# power_supply.net
KiCad netlist of a schematic drawn in Altium Designer
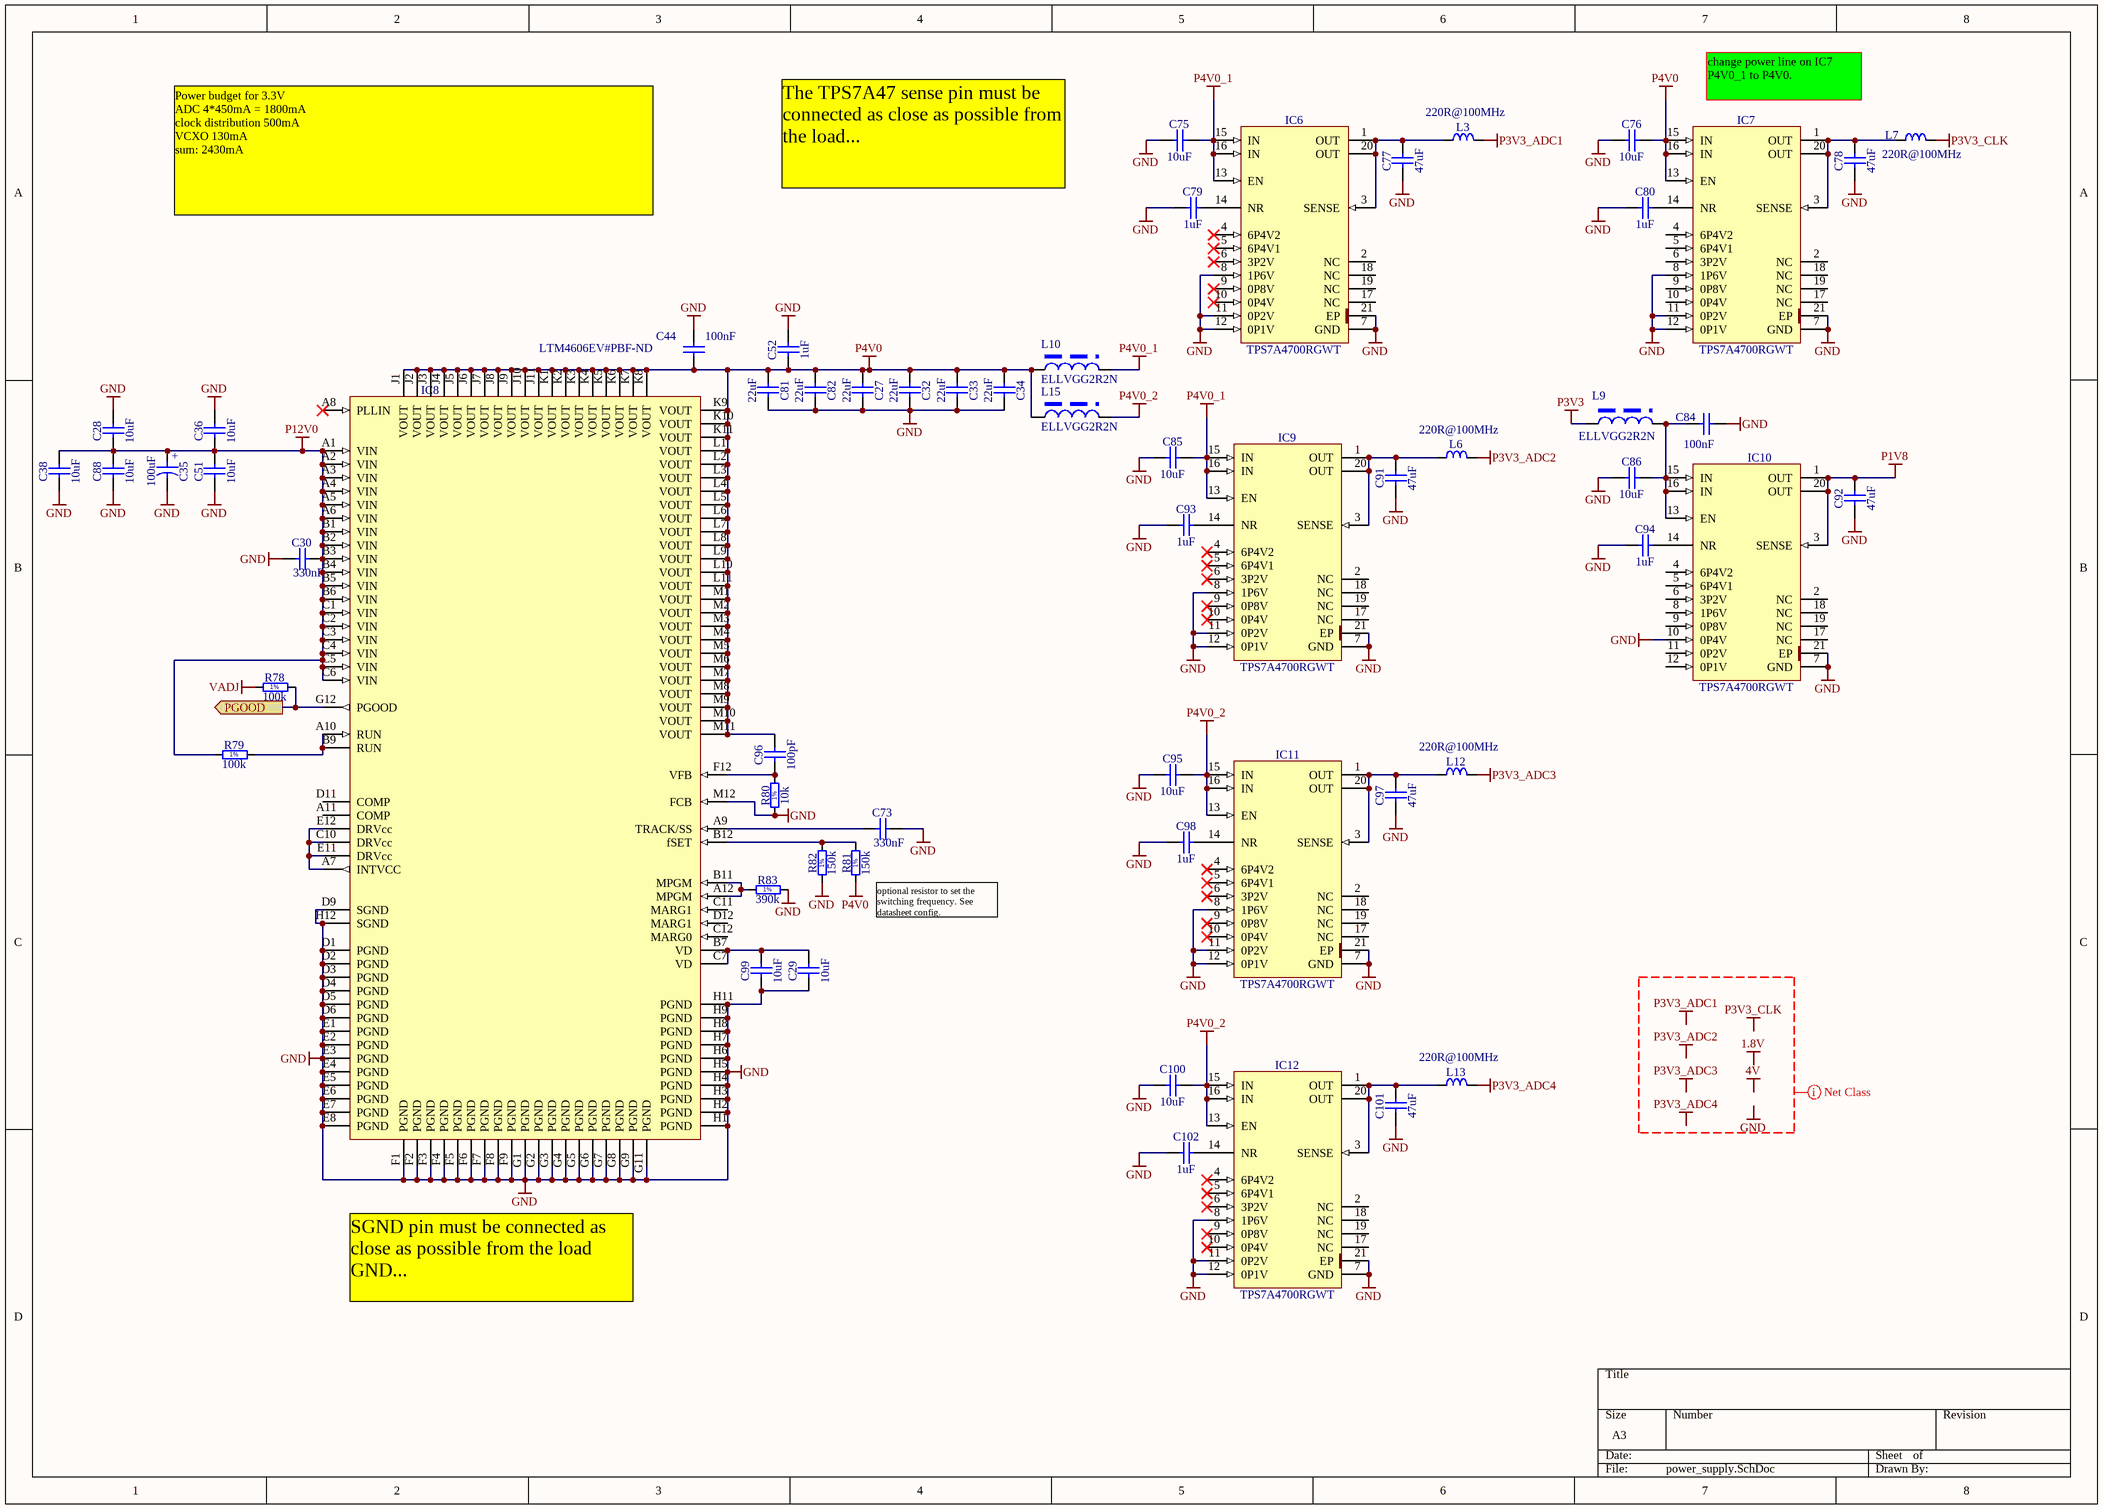
[diagram p0: power_supply.SchDoc]

(export (version "E")
  (design (tool "Eeschema 10.0.6"))
  (components
    (comp (ref "C27")
      (value "22uF")
      (footprint "CAPC3216X140N")
      (description "Non-polarised capacitor")
      (fields
        (field (name "PART NUMBER") "CC1206_22UF_6.3V_20%_X5R")
        (field (name "VOLTAGE") "6.3V")
        (field (name "AUTHOR") "CERN DEM JLC")
      )
      (libsource (lib "Capacitors") (part "Capacitor - non polarized"))
    )
    (comp (ref "C28")
      (value "10uF")
      (footprint "CAPC2012X135N")
      (description "Non-polarised capacitor")
      (fields
        (field (name "PART NUMBER") "CC0805_10UF_16V_10%_X5R")
        (field (name "VOLTAGE") "16V")
        (field (name "AUTHOR") "CERN DEM JLC")
      )
      (libsource (lib "Capacitors") (part "Capacitor - non polarized"))
    )
    (comp (ref "C29")
      (value "10uF")
      (footprint "CAPC2012X135N")
      (description "Non-polarised capacitor")
      (fields
        (field (name "PART NUMBER") "CC0805_10UF_16V_10%_X5R")
        (field (name "VOLTAGE") "16V")
        (field (name "AUTHOR") "CERN DEM JLC")
      )
      (libsource (lib "Capacitors") (part "Capacitor - non polarized"))
    )
    (comp (ref "C30")
      (value "330nF")
      (footprint "CAPC1608X87N")
      (description "Non-polarised capacitor")
      (fields
        (field (name "PART NUMBER") "CC0603_330NF_16V_10%_X5R")
        (field (name "VOLTAGE") "16V")
        (field (name "AUTHOR") "CERN DEM JLC")
      )
      (libsource (lib "Capacitors") (part "Capacitor - non polarized"))
    )
    (comp (ref "C32")
      (value "22uF")
      (footprint "CAPC3216X140N")
      (description "Non-polarised capacitor")
      (fields
        (field (name "PART NUMBER") "CC1206_22UF_6.3V_20%_X5R")
        (field (name "VOLTAGE") "6.3V")
        (field (name "AUTHOR") "CERN DEM JLC")
      )
      (libsource (lib "Capacitors") (part "Capacitor - non polarized"))
    )
    (comp (ref "C33")
      (value "22uF")
      (footprint "CAPC3216X140N")
      (description "Non-polarised capacitor")
      (fields
        (field (name "PART NUMBER") "CC1206_22UF_6.3V_20%_X5R")
        (field (name "VOLTAGE") "6.3V")
        (field (name "AUTHOR") "CERN DEM JLC")
      )
      (libsource (lib "Capacitors") (part "Capacitor - non polarized"))
    )
    (comp (ref "C34")
      (value "22uF")
      (footprint "CAPC3216X140N")
      (description "Non-polarised capacitor")
      (fields
        (field (name "PART NUMBER") "CC1206_22UF_6.3V_20%_X5R")
        (field (name "VOLTAGE") "6.3V")
        (field (name "AUTHOR") "CERN DEM JLC")
      )
      (libsource (lib "Capacitors") (part "Capacitor - non polarized"))
    )
    (comp (ref "C35")
      (value "100uF")
      (footprint "CAPMP7343X310N")
      (description "Polarised capacitor")
      (fields
        (field (name "PART NUMBER") "CTE7343-31_100UF_20V_10%")
        (field (name "VOLTAGE") "20V")
        (field (name "AUTHOR") "CERN DEM JLC")
      )
      (libsource (lib "Capacitors") (part "Capacitor - polarized"))
    )
    (comp (ref "C36")
      (value "10uF")
      (footprint "CAPC2012X135N")
      (description "Non-polarised capacitor")
      (fields
        (field (name "PART NUMBER") "CC0805_10UF_16V_10%_X5R")
        (field (name "VOLTAGE") "16V")
        (field (name "AUTHOR") "CERN DEM JLC")
      )
      (libsource (lib "Capacitors") (part "Capacitor - non polarized"))
    )
    (comp (ref "C38")
      (value "10uF")
      (footprint "CAPC2012X135N")
      (description "Non-polarised capacitor")
      (fields
        (field (name "PART NUMBER") "CC0805_10UF_16V_10%_X5R")
        (field (name "VOLTAGE") "16V")
        (field (name "AUTHOR") "CERN DEM JLC")
      )
      (libsource (lib "Capacitors") (part "Capacitor - non polarized"))
    )
    (comp (ref "C44")
      (value "100nF")
      (footprint "CAPC0603X33N")
      (description "Non-polarised capacitor")
      (fields
        (field (name "PART NUMBER") "CC0201_100NF_6.3V_10%_X5R")
        (field (name "VOLTAGE") "6.3V")
        (field (name "AUTHOR") "CERN DEM JLC")
      )
      (libsource (lib "Capacitors") (part "Capacitor - non polarized"))
    )
    (comp (ref "C51")
      (value "10uF")
      (footprint "CAPC2012X135N")
      (description "Non-polarised capacitor")
      (fields
        (field (name "PART NUMBER") "CC0805_10UF_16V_10%_X5R")
        (field (name "VOLTAGE") "16V")
        (field (name "AUTHOR") "CERN DEM JLC")
      )
      (libsource (lib "Capacitors") (part "Capacitor - non polarized"))
    )
    (comp (ref "C52")
      (value "1uF")
      (footprint "CAPC1608X87N")
      (description "Non-polarised capacitor")
      (fields
        (field (name "PART NUMBER") "CC0603_1UF_25V_10%_X7R")
        (field (name "VOLTAGE") "25V")
        (field (name "AUTHOR") "CERN DEM JLC")
      )
      (libsource (lib "Capacitors") (part "Capacitor - non polarized"))
    )
    (comp (ref "C73")
      (value "330nF")
      (footprint "CAPC1608X87N")
      (description "Non-polarised capacitor")
      (fields
        (field (name "PART NUMBER") "CC0603_330NF_16V_10%_X5R")
        (field (name "VOLTAGE") "16V")
        (field (name "AUTHOR") "CERN DEM JLC")
      )
      (libsource (lib "Capacitors") (part "Capacitor - non polarized"))
    )
    (comp (ref "C75")
      (value "10uF")
      (footprint "CAPC2012X135N")
      (description "Non-polarised capacitor")
      (fields
        (field (name "PART NUMBER") "CC0805_10UF_10V_10%_X7R")
        (field (name "VOLTAGE") "10V")
        (field (name "AUTHOR") "CERN DEM JLC")
      )
      (libsource (lib "Capacitors") (part "Capacitor - non polarized"))
    )
    (comp (ref "C76")
      (value "10uF")
      (footprint "CAPC2012X135N")
      (description "Non-polarised capacitor")
      (fields
        (field (name "PART NUMBER") "CC0805_10UF_10V_10%_X7R")
        (field (name "VOLTAGE") "10V")
        (field (name "AUTHOR") "CERN DEM JLC")
      )
      (libsource (lib "Capacitors") (part "Capacitor - non polarized"))
    )
    (comp (ref "C77")
      (value "47uF")
      (footprint "CAPC2012X140N")
      (description "Non-polarised capacitor")
      (fields
        (field (name "PART NUMBER") "CC0805_47UF_6.3V_20%_X5R")
        (field (name "VOLTAGE") "6.3V")
        (field (name "AUTHOR") "CERN DEM JLC")
      )
      (libsource (lib "Capacitors") (part "Capacitor - non polarized"))
    )
    (comp (ref "C78")
      (value "47uF")
      (footprint "CAPC2012X140N")
      (description "Non-polarised capacitor")
      (fields
        (field (name "PART NUMBER") "CC0805_47UF_6.3V_20%_X5R")
        (field (name "VOLTAGE") "6.3V")
        (field (name "AUTHOR") "CERN DEM JLC")
      )
      (libsource (lib "Capacitors") (part "Capacitor - non polarized"))
    )
    (comp (ref "C79")
      (value "1uF")
      (footprint "CAPC1608X87N")
      (description "Non-polarised capacitor")
      (fields
        (field (name "PART NUMBER") "CC0603_1UF_25V_10%_X7R")
        (field (name "VOLTAGE") "25V")
        (field (name "AUTHOR") "CERN DEM JLC")
      )
      (libsource (lib "Capacitors") (part "Capacitor - non polarized"))
    )
    (comp (ref "C80")
      (value "1uF")
      (footprint "CAPC1608X87N")
      (description "Non-polarised capacitor")
      (fields
        (field (name "PART NUMBER") "CC0603_1UF_25V_10%_X7R")
        (field (name "VOLTAGE") "25V")
        (field (name "AUTHOR") "CERN DEM JLC")
      )
      (libsource (lib "Capacitors") (part "Capacitor - non polarized"))
    )
    (comp (ref "C81")
      (value "22uF")
      (footprint "CAPC3216X140N")
      (description "Non-polarised capacitor")
      (fields
        (field (name "PART NUMBER") "CC1206_22UF_6.3V_20%_X5R")
        (field (name "VOLTAGE") "6.3V")
        (field (name "AUTHOR") "CERN DEM JLC")
      )
      (libsource (lib "Capacitors") (part "Capacitor - non polarized"))
    )
    (comp (ref "C82")
      (value "22uF")
      (footprint "CAPC3216X140N")
      (description "Non-polarised capacitor")
      (fields
        (field (name "PART NUMBER") "CC1206_22UF_6.3V_20%_X5R")
        (field (name "VOLTAGE") "6.3V")
        (field (name "AUTHOR") "CERN DEM JLC")
      )
      (libsource (lib "Capacitors") (part "Capacitor - non polarized"))
    )
    (comp (ref "C84")
      (value "100nF")
      (footprint "CAPC0603X33N")
      (description "Non-polarised capacitor")
      (fields
        (field (name "PART NUMBER") "CC0201_100NF_6.3V_10%_X5R")
        (field (name "VOLTAGE") "6.3V")
        (field (name "AUTHOR") "CERN DEM JLC")
      )
      (libsource (lib "Capacitors") (part "Capacitor - non polarized"))
    )
    (comp (ref "C85")
      (value "10uF")
      (footprint "CAPC2012X135N")
      (description "Non-polarised capacitor")
      (fields
        (field (name "PART NUMBER") "CC0805_10UF_10V_10%_X7R")
        (field (name "VOLTAGE") "10V")
        (field (name "AUTHOR") "CERN DEM JLC")
      )
      (libsource (lib "Capacitors") (part "Capacitor - non polarized"))
    )
    (comp (ref "C86")
      (value "10uF")
      (footprint "CAPC2012X135N")
      (description "Non-polarised capacitor")
      (fields
        (field (name "PART NUMBER") "CC0805_10UF_10V_10%_X7R")
        (field (name "VOLTAGE") "10V")
        (field (name "AUTHOR") "CERN DEM JLC")
      )
      (libsource (lib "Capacitors") (part "Capacitor - non polarized"))
    )
    (comp (ref "C88")
      (value "10uF")
      (footprint "CAPC2012X135N")
      (description "Non-polarised capacitor")
      (fields
        (field (name "PART NUMBER") "CC0805_10UF_16V_10%_X5R")
        (field (name "VOLTAGE") "16V")
        (field (name "AUTHOR") "CERN DEM JLC")
      )
      (libsource (lib "Capacitors") (part "Capacitor - non polarized"))
    )
    (comp (ref "C91")
      (value "47uF")
      (footprint "CAPC2012X140N")
      (description "Non-polarised capacitor")
      (fields
        (field (name "PART NUMBER") "CC0805_47UF_6.3V_20%_X5R")
        (field (name "VOLTAGE") "6.3V")
        (field (name "AUTHOR") "CERN DEM JLC")
      )
      (libsource (lib "Capacitors") (part "Capacitor - non polarized"))
    )
    (comp (ref "C92")
      (value "47uF")
      (footprint "CAPC2012X140N")
      (description "Non-polarised capacitor")
      (fields
        (field (name "PART NUMBER") "CC0805_47UF_6.3V_20%_X5R")
        (field (name "VOLTAGE") "6.3V")
        (field (name "AUTHOR") "CERN DEM JLC")
      )
      (libsource (lib "Capacitors") (part "Capacitor - non polarized"))
    )
    (comp (ref "C93")
      (value "1uF")
      (footprint "CAPC1608X87N")
      (description "Non-polarised capacitor")
      (fields
        (field (name "PART NUMBER") "CC0603_1UF_25V_10%_X7R")
        (field (name "VOLTAGE") "25V")
        (field (name "AUTHOR") "CERN DEM JLC")
      )
      (libsource (lib "Capacitors") (part "Capacitor - non polarized"))
    )
    (comp (ref "C94")
      (value "1uF")
      (footprint "CAPC1608X87N")
      (description "Non-polarised capacitor")
      (fields
        (field (name "PART NUMBER") "CC0603_1UF_25V_10%_X7R")
        (field (name "VOLTAGE") "25V")
        (field (name "AUTHOR") "CERN DEM JLC")
      )
      (libsource (lib "Capacitors") (part "Capacitor - non polarized"))
    )
    (comp (ref "C95")
      (value "10uF")
      (footprint "CAPC2012X135N")
      (description "Non-polarised capacitor")
      (fields
        (field (name "PART NUMBER") "CC0805_10UF_10V_10%_X7R")
        (field (name "VOLTAGE") "10V")
        (field (name "AUTHOR") "CERN DEM JLC")
      )
      (libsource (lib "Capacitors") (part "Capacitor - non polarized"))
    )
    (comp (ref "C96")
      (value "100pF")
      (footprint "CAPC1005X55N")
      (description "Non-polarised capacitor")
      (fields
        (field (name "PART NUMBER") "CC0402_100PF_50V_5%_NP0")
        (field (name "VOLTAGE") "50V")
        (field (name "AUTHOR") "CERN DEM JLC")
      )
      (libsource (lib "Capacitors") (part "Capacitor - non polarized"))
    )
    (comp (ref "C97")
      (value "47uF")
      (footprint "CAPC2012X140N")
      (description "Non-polarised capacitor")
      (fields
        (field (name "PART NUMBER") "CC0805_47UF_6.3V_20%_X5R")
        (field (name "VOLTAGE") "6.3V")
        (field (name "AUTHOR") "CERN DEM JLC")
      )
      (libsource (lib "Capacitors") (part "Capacitor - non polarized"))
    )
    (comp (ref "C98")
      (value "1uF")
      (footprint "CAPC1608X87N")
      (description "Non-polarised capacitor")
      (fields
        (field (name "PART NUMBER") "CC0603_1UF_25V_10%_X7R")
        (field (name "VOLTAGE") "25V")
        (field (name "AUTHOR") "CERN DEM JLC")
      )
      (libsource (lib "Capacitors") (part "Capacitor - non polarized"))
    )
    (comp (ref "C99")
      (value "10uF")
      (footprint "CAPC2012X135N")
      (description "Non-polarised capacitor")
      (fields
        (field (name "PART NUMBER") "CC0805_10UF_16V_10%_X5R")
        (field (name "VOLTAGE") "16V")
        (field (name "AUTHOR") "CERN DEM JLC")
      )
      (libsource (lib "Capacitors") (part "Capacitor - non polarized"))
    )
    (comp (ref "C100")
      (value "10uF")
      (footprint "CAPC2012X135N")
      (description "Non-polarised capacitor")
      (fields
        (field (name "PART NUMBER") "CC0805_10UF_10V_10%_X7R")
        (field (name "VOLTAGE") "10V")
        (field (name "AUTHOR") "CERN DEM JLC")
      )
      (libsource (lib "Capacitors") (part "Capacitor - non polarized"))
    )
    (comp (ref "C101")
      (value "47uF")
      (footprint "CAPC2012X140N")
      (description "Non-polarised capacitor")
      (fields
        (field (name "PART NUMBER") "CC0805_47UF_6.3V_20%_X5R")
        (field (name "VOLTAGE") "6.3V")
        (field (name "AUTHOR") "CERN DEM JLC")
      )
      (libsource (lib "Capacitors") (part "Capacitor - non polarized"))
    )
    (comp (ref "C102")
      (value "1uF")
      (footprint "CAPC1608X87N")
      (description "Non-polarised capacitor")
      (fields
        (field (name "PART NUMBER") "CC0603_1UF_25V_10%_X7R")
        (field (name "VOLTAGE") "25V")
        (field (name "AUTHOR") "CERN DEM JLC")
      )
      (libsource (lib "Capacitors") (part "Capacitor - non polarized"))
    )
    (comp (ref "IC6")
      (value "TPS7A4700RGWT")
      (footprint "QFN65P500X500X100-21N-S325")
      (description "Low Noise (3uVrms), 1A, High Voltage Low-Dropout Linear Regulator")
      (fields (field (name "MANUFACTURER") "TEXAS INSTRUMENTS") (field (name "AUTHOR") "CERN DEM JLC"))
      (libsource (lib "ICs And Semiconductors") (part "TPS7A4700RGW"))
    )
    (comp (ref "IC7")
      (value "TPS7A4700RGWT")
      (footprint "QFN65P500X500X100-21N-S325")
      (description "Low Noise (3uVrms), 1A, High Voltage Low-Dropout Linear Regulator")
      (fields (field (name "MANUFACTURER") "TEXAS INSTRUMENTS") (field (name "AUTHOR") "CERN DEM JLC"))
      (libsource (lib "ICs And Semiconductors") (part "TPS7A4700RGW"))
    )
    (comp (ref "IC8")
      (value "LTM4606EV#PBF-ND")
      (footprint "LTM4606")
      (description "4.5V-20V To 0.6V-5V, Iout 6A DC/DC low EMI uModule")
      (fields (field (name "SUPPLIER PART NUMBER 1") "LTM4606EV#PBF-ND"))
      (libsource (lib "fmclib") (part "LTM4601"))
    )
    (comp (ref "IC9")
      (value "TPS7A4700RGWT")
      (footprint "QFN65P500X500X100-21N-S325")
      (description "Low Noise (3uVrms), 1A, High Voltage Low-Dropout Linear Regulator")
      (fields (field (name "MANUFACTURER") "TEXAS INSTRUMENTS") (field (name "AUTHOR") "CERN DEM JLC"))
      (libsource (lib "ICs And Semiconductors") (part "TPS7A4700RGW"))
    )
    (comp (ref "IC10")
      (value "TPS7A4700RGWT")
      (footprint "QFN65P500X500X100-21N-S325")
      (description "Low Noise (3uVrms), 1A, High Voltage Low-Dropout Linear Regulator")
      (fields (field (name "MANUFACTURER") "TEXAS INSTRUMENTS") (field (name "AUTHOR") "CERN DEM JLC"))
      (libsource (lib "ICs And Semiconductors") (part "TPS7A4700RGW"))
    )
    (comp (ref "IC11")
      (value "TPS7A4700RGWT")
      (footprint "QFN65P500X500X100-21N-S325")
      (description "Low Noise (3uVrms), 1A, High Voltage Low-Dropout Linear Regulator")
      (fields (field (name "MANUFACTURER") "TEXAS INSTRUMENTS") (field (name "AUTHOR") "CERN DEM JLC"))
      (libsource (lib "ICs And Semiconductors") (part "TPS7A4700RGW"))
    )
    (comp (ref "IC12")
      (value "TPS7A4700RGWT")
      (footprint "QFN65P500X500X100-21N-S325")
      (description "Low Noise (3uVrms), 1A, High Voltage Low-Dropout Linear Regulator")
      (fields (field (name "MANUFACTURER") "TEXAS INSTRUMENTS") (field (name "AUTHOR") "CERN DEM JLC"))
      (libsource (lib "ICs And Semiconductors") (part "TPS7A4700RGW"))
    )
    (comp (ref "L3")
      (value "220R@100MHz")
      (footprint "INDC2012X105N")
      (description "Inductor")
      (fields
        (field (name "PART NUMBER") "IND0805_MURATA_BLM21PG221SN1D")
        (field (name "POWER") "2A")
        (field (name "AUTHOR") "CERN DEM JLC")
      )
      (libsource (lib "Inductors & Transformers") (part "Inductor"))
    )
    (comp (ref "L6")
      (value "220R@100MHz")
      (footprint "INDC2012X105N")
      (description "Inductor")
      (fields
        (field (name "PART NUMBER") "IND0805_MURATA_BLM21PG221SN1D")
        (field (name "POWER") "2A")
        (field (name "AUTHOR") "CERN DEM JLC")
      )
      (libsource (lib "Inductors & Transformers") (part "Inductor"))
    )
    (comp (ref "L7")
      (value "220R@100MHz")
      (footprint "INDC2012X105N")
      (description "Inductor")
      (fields
        (field (name "PART NUMBER") "IND0805_MURATA_BLM21PG221SN1D")
        (field (name "POWER") "2A")
        (field (name "AUTHOR") "CERN DEM JLC")
      )
      (libsource (lib "Inductors & Transformers") (part "Inductor"))
    )
    (comp (ref "L9")
      (value "ELLVGG2R2N")
      (footprint "L_ELLVGG2R2N")
      (description "2.2uH, 1.4A, 92mR Panasonic")
      (libsource (lib "LIBRARY_SCH") (part "L_CHOKE_ELLVGG"))
    )
    (comp (ref "L10")
      (value "ELLVGG2R2N")
      (footprint "L_ELLVGG2R2N")
      (description "2.2uH, 1.4A, 92mR Panasonic")
      (libsource (lib "LIBRARY_SCH") (part "L_CHOKE_ELLVGG"))
    )
    (comp (ref "L12")
      (value "220R@100MHz")
      (footprint "INDC2012X105N")
      (description "Inductor")
      (fields
        (field (name "PART NUMBER") "IND0805_MURATA_BLM21PG221SN1D")
        (field (name "POWER") "2A")
        (field (name "AUTHOR") "CERN DEM JLC")
      )
      (libsource (lib "Inductors & Transformers") (part "Inductor"))
    )
    (comp (ref "L13")
      (value "220R@100MHz")
      (footprint "INDC2012X105N")
      (description "Inductor")
      (fields
        (field (name "PART NUMBER") "IND0805_MURATA_BLM21PG221SN1D")
        (field (name "POWER") "2A")
        (field (name "AUTHOR") "CERN DEM JLC")
      )
      (libsource (lib "Inductors & Transformers") (part "Inductor"))
    )
    (comp (ref "L15")
      (value "ELLVGG2R2N")
      (footprint "L_ELLVGG2R2N")
      (description "2.2uH, 1.4A, 92mR Panasonic")
      (libsource (lib "LIBRARY_SCH") (part "L_CHOKE_ELLVGG"))
    )
    (comp (ref "R78")
      (value "100k")
      (footprint "RESC1005X40N")
      (description "Resistor - 1%")
      (fields
        (field (name "PART NUMBER") "R0402_100K_1%_0.0625W_100PPM")
        (field (name "POWER") "0.0625W")
        (field (name "AUTHOR") "CERN DEM JLC")
      )
      (libsource (lib "Resistors") (part "Resistor - 1%"))
    )
    (comp (ref "R79")
      (value "100k")
      (footprint "RESC1005X40N")
      (description "Resistor - 1%")
      (fields
        (field (name "PART NUMBER") "R0402_100K_1%_0.0625W_100PPM")
        (field (name "POWER") "0.0625W")
        (field (name "AUTHOR") "CERN DEM JLC")
      )
      (libsource (lib "Resistors") (part "Resistor - 1%"))
    )
    (comp (ref "R80")
      (value "10k")
      (footprint "RESC1005X40N")
      (description "Resistor - 1%")
      (fields
        (field (name "PART NUMBER") "R0402_10K_1%_0.0625W_100PPM")
        (field (name "POWER") "0.0625W")
        (field (name "AUTHOR") "CERN DEM JLC")
      )
      (libsource (lib "") (part "Resistor - 1%_1"))
    )
    (comp (ref "R81")
      (value "150k")
      (footprint "RESC1005X40N")
      (description "Resistor - 1%")
      (fields
        (field (name "PART NUMBER") "R0402_150K_1%_0.0625W_100PPM")
        (field (name "POWER") "0.0625W")
        (field (name "AUTHOR") "CERN DEM JLC")
      )
      (libsource (lib "Resistors") (part "Resistor - 1%"))
    )
    (comp (ref "R82")
      (value "150k")
      (footprint "RESC1005X40N")
      (description "Resistor - 1%")
      (fields
        (field (name "PART NUMBER") "R0402_150K_1%_0.0625W_100PPM")
        (field (name "POWER") "0.0625W")
        (field (name "AUTHOR") "CERN DEM JLC")
      )
      (libsource (lib "Resistors") (part "Resistor - 1%"))
    )
    (comp (ref "R83")
      (value "390k")
      (footprint "RESC1005X40N")
      (description "Resistor - 1%")
      (fields
        (field (name "PART NUMBER") "R0402_390K_1%_0.0625W_100PPM")
        (field (name "POWER") "0.0625W")
        (field (name "AUTHOR") "CERN DEM JLC")
      )
      (libsource (lib "Resistors") (part "Resistor - 1%"))
    )
  )
  (nets
    (net (code "1") (name "/PGOOD") (class "Default")
      (node (ref "IC8") (pin "G12") (pinfunction "PGOOD_G12") (pintype "output"))
      (node (ref "R78") (pin "2") (pinfunction "2_2") (pintype "passive"))
    )
    (net (code "4") (name "GND") (class "Default")
      (node (ref "C100") (pin "1") (pinfunction "1_1") (pintype "passive"))
      (node (ref "C101") (pin "1") (pinfunction "1_1") (pintype "passive"))
      (node (ref "C102") (pin "1") (pinfunction "1_1") (pintype "passive"))
      (node (ref "C27") (pin "2") (pinfunction "2_2") (pintype "passive"))
      (node (ref "C28") (pin "2") (pinfunction "2_2") (pintype "passive"))
      (node (ref "C29") (pin "1") (pinfunction "1_1") (pintype "passive"))
      (node (ref "C30") (pin "1") (pinfunction "1_1") (pintype "passive"))
      (node (ref "C32") (pin "2") (pinfunction "2_2") (pintype "passive"))
      (node (ref "C33") (pin "2") (pinfunction "2_2") (pintype "passive"))
      (node (ref "C34") (pin "2") (pinfunction "2_2") (pintype "passive"))
      (node (ref "C35") (pin "2") (pinfunction "2_2") (pintype "passive"))
      (node (ref "C36") (pin "2") (pinfunction "2_2") (pintype "passive"))
      (node (ref "C38") (pin "1") (pinfunction "1_1") (pintype "passive"))
      (node (ref "C44") (pin "1") (pinfunction "1_1") (pintype "passive"))
      (node (ref "C51") (pin "1") (pinfunction "1_1") (pintype "passive"))
      (node (ref "C52") (pin "2") (pinfunction "2_2") (pintype "passive"))
      (node (ref "C73") (pin "2") (pinfunction "2_2") (pintype "passive"))
      (node (ref "C75") (pin "1") (pinfunction "1_1") (pintype "passive"))
      (node (ref "C76") (pin "1") (pinfunction "1_1") (pintype "passive"))
      (node (ref "C77") (pin "1") (pinfunction "1_1") (pintype "passive"))
      (node (ref "C78") (pin "1") (pinfunction "1_1") (pintype "passive"))
      (node (ref "C79") (pin "1") (pinfunction "1_1") (pintype "passive"))
      (node (ref "C80") (pin "1") (pinfunction "1_1") (pintype "passive"))
      (node (ref "C81") (pin "2") (pinfunction "2_2") (pintype "passive"))
      (node (ref "C82") (pin "2") (pinfunction "2_2") (pintype "passive"))
      (node (ref "C84") (pin "1") (pinfunction "1_1") (pintype "passive"))
      (node (ref "C85") (pin "1") (pinfunction "1_1") (pintype "passive"))
      (node (ref "C86") (pin "1") (pinfunction "1_1") (pintype "passive"))
      (node (ref "C88") (pin "1") (pinfunction "1_1") (pintype "passive"))
      (node (ref "C91") (pin "1") (pinfunction "1_1") (pintype "passive"))
      (node (ref "C92") (pin "1") (pinfunction "1_1") (pintype "passive"))
      (node (ref "C93") (pin "1") (pinfunction "1_1") (pintype "passive"))
      (node (ref "C94") (pin "1") (pinfunction "1_1") (pintype "passive"))
      (node (ref "C95") (pin "1") (pinfunction "1_1") (pintype "passive"))
      (node (ref "C97") (pin "1") (pinfunction "1_1") (pintype "passive"))
      (node (ref "C98") (pin "1") (pinfunction "1_1") (pintype "passive"))
      (node (ref "C99") (pin "1") (pinfunction "1_1") (pintype "passive"))
      (node (ref "IC10") (pin "10") (pinfunction "0P4V_10") (pintype "input"))
      (node (ref "IC10") (pin "21") (pinfunction "EP_21") (pintype "power_in"))
      (node (ref "IC10") (pin "7") (pinfunction "GND_7") (pintype "power_in"))
      (node (ref "IC11") (pin "11") (pinfunction "0P2V_11") (pintype "input"))
      (node (ref "IC11") (pin "12") (pinfunction "0P1V_12") (pintype "input"))
      (node (ref "IC11") (pin "21") (pinfunction "EP_21") (pintype "power_in"))
      (node (ref "IC11") (pin "7") (pinfunction "GND_7") (pintype "power_in"))
      (node (ref "IC11") (pin "8") (pinfunction "1P6V_8") (pintype "input"))
      (node (ref "IC12") (pin "11") (pinfunction "0P2V_11") (pintype "input"))
      (node (ref "IC12") (pin "12") (pinfunction "0P1V_12") (pintype "input"))
      (node (ref "IC12") (pin "21") (pinfunction "EP_21") (pintype "power_in"))
      (node (ref "IC12") (pin "7") (pinfunction "GND_7") (pintype "power_in"))
      (node (ref "IC12") (pin "8") (pinfunction "1P6V_8") (pintype "input"))
      (node (ref "IC6") (pin "11") (pinfunction "0P2V_11") (pintype "input"))
      (node (ref "IC6") (pin "12") (pinfunction "0P1V_12") (pintype "input"))
      (node (ref "IC6") (pin "21") (pinfunction "EP_21") (pintype "power_in"))
      (node (ref "IC6") (pin "7") (pinfunction "GND_7") (pintype "power_in"))
      (node (ref "IC6") (pin "8") (pinfunction "1P6V_8") (pintype "input"))
      (node (ref "IC7") (pin "11") (pinfunction "0P2V_11") (pintype "input"))
      (node (ref "IC7") (pin "12") (pinfunction "0P1V_12") (pintype "input"))
      (node (ref "IC7") (pin "21") (pinfunction "EP_21") (pintype "power_in"))
      (node (ref "IC7") (pin "7") (pinfunction "GND_7") (pintype "power_in"))
      (node (ref "IC7") (pin "8") (pinfunction "1P6V_8") (pintype "input"))
      (node (ref "IC8") (pin "D1") (pinfunction "PGND_D1") (pintype "power_in"))
      (node (ref "IC8") (pin "D2") (pinfunction "PGND_D2") (pintype "power_in"))
      (node (ref "IC8") (pin "D3") (pinfunction "PGND_D3") (pintype "power_in"))
      (node (ref "IC8") (pin "D4") (pinfunction "PGND_D4") (pintype "power_in"))
      (node (ref "IC8") (pin "D5") (pinfunction "PGND_D5") (pintype "power_in"))
      (node (ref "IC8") (pin "D6") (pinfunction "PGND_D6") (pintype "power_in"))
      (node (ref "IC8") (pin "D9") (pinfunction "SGND_D9") (pintype "power_in"))
      (node (ref "IC8") (pin "E1") (pinfunction "PGND_E1") (pintype "power_in"))
      (node (ref "IC8") (pin "E2") (pinfunction "PGND_E2") (pintype "power_in"))
      (node (ref "IC8") (pin "E3") (pinfunction "PGND_E3") (pintype "power_in"))
      (node (ref "IC8") (pin "E4") (pinfunction "PGND_E4") (pintype "power_in"))
      (node (ref "IC8") (pin "E5") (pinfunction "PGND_E5") (pintype "power_in"))
      (node (ref "IC8") (pin "E6") (pinfunction "PGND_E6") (pintype "power_in"))
      (node (ref "IC8") (pin "E7") (pinfunction "PGND_E7") (pintype "power_in"))
      (node (ref "IC8") (pin "E8") (pinfunction "PGND_E8") (pintype "power_in"))
      (node (ref "IC8") (pin "F1") (pinfunction "PGND_F1") (pintype "power_in"))
      (node (ref "IC8") (pin "F2") (pinfunction "PGND_F2") (pintype "power_in"))
      (node (ref "IC8") (pin "F3") (pinfunction "PGND_F3") (pintype "power_in"))
      (node (ref "IC8") (pin "F4") (pinfunction "PGND_F4") (pintype "power_in"))
      (node (ref "IC8") (pin "F5") (pinfunction "PGND_F5") (pintype "power_in"))
      (node (ref "IC8") (pin "F6") (pinfunction "PGND_F6") (pintype "power_in"))
      (node (ref "IC8") (pin "F7") (pinfunction "PGND_F7") (pintype "power_in"))
      (node (ref "IC8") (pin "F8") (pinfunction "PGND_F8") (pintype "power_in"))
      (node (ref "IC8") (pin "F9") (pinfunction "PGND_F9") (pintype "power_in"))
      (node (ref "IC8") (pin "G1") (pinfunction "PGND_G1") (pintype "power_in"))
      (node (ref "IC8") (pin "G11") (pinfunction "PGND_G11") (pintype "power_in"))
      (node (ref "IC8") (pin "G2") (pinfunction "PGND_G2") (pintype "power_in"))
      (node (ref "IC8") (pin "G3") (pinfunction "PGND_G3") (pintype "power_in"))
      (node (ref "IC8") (pin "G4") (pinfunction "PGND_G4") (pintype "power_in"))
      (node (ref "IC8") (pin "G5") (pinfunction "PGND_G5") (pintype "power_in"))
      (node (ref "IC8") (pin "G6") (pinfunction "PGND_G6") (pintype "power_in"))
      (node (ref "IC8") (pin "G7") (pinfunction "PGND_G7") (pintype "power_in"))
      (node (ref "IC8") (pin "G8") (pinfunction "PGND_G8") (pintype "power_in"))
      (node (ref "IC8") (pin "G9") (pinfunction "PGND_G9") (pintype "power_in"))
      (node (ref "IC8") (pin "H1") (pinfunction "PGND_H1") (pintype "power_in"))
      (node (ref "IC8") (pin "H11") (pinfunction "PGND_H11") (pintype "passive"))
      (node (ref "IC8") (pin "H12") (pinfunction "SGND_H12") (pintype "power_in"))
      (node (ref "IC8") (pin "H2") (pinfunction "PGND_H2") (pintype "power_in"))
      (node (ref "IC8") (pin "H3") (pinfunction "PGND_H3") (pintype "power_in"))
      (node (ref "IC8") (pin "H4") (pinfunction "PGND_H4") (pintype "power_in"))
      (node (ref "IC8") (pin "H5") (pinfunction "PGND_H5") (pintype "power_in"))
      (node (ref "IC8") (pin "H6") (pinfunction "PGND_H6") (pintype "power_in"))
      (node (ref "IC8") (pin "H7") (pinfunction "PGND_H7") (pintype "power_in"))
      (node (ref "IC8") (pin "H8") (pinfunction "PGND_H8") (pintype "power_in"))
      (node (ref "IC8") (pin "H9") (pinfunction "PGND_H9") (pintype "power_in"))
      (node (ref "IC8") (pin "M12") (pinfunction "FCB_M12") (pintype "input"))
      (node (ref "IC9") (pin "11") (pinfunction "0P2V_11") (pintype "input"))
      (node (ref "IC9") (pin "12") (pinfunction "0P1V_12") (pintype "input"))
      (node (ref "IC9") (pin "21") (pinfunction "EP_21") (pintype "power_in"))
      (node (ref "IC9") (pin "7") (pinfunction "GND_7") (pintype "power_in"))
      (node (ref "IC9") (pin "8") (pinfunction "1P6V_8") (pintype "input"))
      (node (ref "R80") (pin "2") (pinfunction "2_2") (pintype "passive"))
      (node (ref "R82") (pin "1") (pinfunction "1_1") (pintype "passive"))
      (node (ref "R83") (pin "2") (pinfunction "2_2") (pintype "passive"))
    )
    (net (code "5") (name "Net-(C29-Pad2)") (class "Default")
      (node (ref "C29") (pin "2") (pinfunction "2_2") (pintype "passive"))
      (node (ref "C99") (pin "2") (pinfunction "2_2") (pintype "passive"))
      (node (ref "IC8") (pin "B7") (pinfunction "VD_B7") (pintype "passive"))
      (node (ref "IC8") (pin "C7") (pinfunction "VD_C7") (pintype "passive"))
    )
    (net (code "6") (name "Net-(IC6-NR)") (class "Default")
      (node (ref "C79") (pin "2") (pinfunction "2_2") (pintype "passive"))
      (node (ref "IC6") (pin "14") (pinfunction "NR_14") (pintype "passive"))
    )
    (net (code "7") (name "Net-(IC6-SENSE)") (class "Default")
      (node (ref "C77") (pin "2") (pinfunction "2_2") (pintype "passive"))
      (node (ref "IC6") (pin "1") (pinfunction "OUT_1") (pintype "power_in"))
      (node (ref "IC6") (pin "20") (pinfunction "OUT_20") (pintype "power_in"))
      (node (ref "IC6") (pin "3") (pinfunction "SENSE_3") (pintype "input"))
      (node (ref "L3") (pin "1") (pinfunction "1_1") (pintype "passive"))
    )
    (net (code "8") (name "Net-(IC7-NR)") (class "Default")
      (node (ref "C80") (pin "2") (pinfunction "2_2") (pintype "passive"))
      (node (ref "IC7") (pin "14") (pinfunction "NR_14") (pintype "passive"))
    )
    (net (code "9") (name "Net-(IC7-SENSE)") (class "Default")
      (node (ref "C78") (pin "2") (pinfunction "2_2") (pintype "passive"))
      (node (ref "IC7") (pin "1") (pinfunction "OUT_1") (pintype "power_in"))
      (node (ref "IC7") (pin "20") (pinfunction "OUT_20") (pintype "power_in"))
      (node (ref "IC7") (pin "3") (pinfunction "SENSE_3") (pintype "input"))
      (node (ref "L7") (pin "1") (pinfunction "1_1") (pintype "passive"))
    )
    (net (code "10") (name "Net-(IC8-INTVCC)") (class "Default")
      (node (ref "IC8") (pin "A7") (pinfunction "INTVCC_A7") (pintype "output"))
      (node (ref "IC8") (pin "C10") (pinfunction "DRVcc_C10") (pintype "power_in"))
      (node (ref "IC8") (pin "E11") (pinfunction "DRVcc_E11") (pintype "power_in"))
      (node (ref "IC8") (pin "E12") (pinfunction "DRVcc_E12") (pintype "power_in"))
    )
    (net (code "11") (name "Net-(IC8-MPGM-PadA12)") (class "Default")
      (node (ref "IC8") (pin "A12") (pinfunction "MPGM_A12") (pintype "input"))
      (node (ref "IC8") (pin "B11") (pinfunction "MPGM_B11") (pintype "input"))
      (node (ref "R83") (pin "1") (pinfunction "1_1") (pintype "passive"))
    )
    (net (code "12") (name "Net-(IC8-RUN-PadA10)") (class "Default")
      (node (ref "IC8") (pin "A10") (pinfunction "RUN_A10") (pintype "input"))
      (node (ref "IC8") (pin "B9") (pinfunction "RUN_B9") (pintype "open_collector"))
      (node (ref "R79") (pin "2") (pinfunction "2_2") (pintype "passive"))
    )
    (net (code "13") (name "Net-(IC8-TRACK{slash}SS)") (class "Default")
      (node (ref "C73") (pin "1") (pinfunction "1_1") (pintype "passive"))
      (node (ref "IC8") (pin "A9") (pinfunction "TRACK/SS_A9") (pintype "input"))
    )
    (net (code "14") (name "Net-(IC8-VFB)") (class "Default")
      (node (ref "C96") (pin "1") (pinfunction "1_1") (pintype "passive"))
      (node (ref "IC8") (pin "F12") (pinfunction "VFB_F12") (pintype "input"))
      (node (ref "R80") (pin "1") (pinfunction "1_1") (pintype "passive"))
    )
    (net (code "15") (name "Net-(IC8-fSET)") (class "Default")
      (node (ref "IC8") (pin "B12") (pinfunction "fSET_B12") (pintype "input"))
      (node (ref "R81") (pin "2") (pinfunction "2_2") (pintype "passive"))
      (node (ref "R82") (pin "2") (pinfunction "2_2") (pintype "passive"))
    )
    (net (code "16") (name "Net-(IC9-NR)") (class "Default")
      (node (ref "C93") (pin "2") (pinfunction "2_2") (pintype "passive"))
      (node (ref "IC9") (pin "14") (pinfunction "NR_14") (pintype "passive"))
    )
    (net (code "17") (name "Net-(IC9-SENSE)") (class "Default")
      (node (ref "C91") (pin "2") (pinfunction "2_2") (pintype "passive"))
      (node (ref "IC9") (pin "1") (pinfunction "OUT_1") (pintype "power_in"))
      (node (ref "IC9") (pin "20") (pinfunction "OUT_20") (pintype "power_in"))
      (node (ref "IC9") (pin "3") (pinfunction "SENSE_3") (pintype "input"))
      (node (ref "L6") (pin "1") (pinfunction "1_1") (pintype "passive"))
    )
    (net (code "18") (name "Net-(IC10-EN)") (class "Default")
      (node (ref "C84") (pin "2") (pinfunction "2_2") (pintype "passive"))
      (node (ref "C86") (pin "2") (pinfunction "2_2") (pintype "passive"))
      (node (ref "IC10") (pin "13") (pinfunction "EN_13") (pintype "input"))
      (node (ref "IC10") (pin "15") (pinfunction "IN_15") (pintype "input"))
      (node (ref "IC10") (pin "16") (pinfunction "IN_16") (pintype "input"))
      (node (ref "L9") (pin "2") (pintype "passive"))
    )
    (net (code "19") (name "Net-(IC10-NR)") (class "Default")
      (node (ref "C94") (pin "2") (pinfunction "2_2") (pintype "passive"))
      (node (ref "IC10") (pin "14") (pinfunction "NR_14") (pintype "passive"))
    )
    (net (code "20") (name "Net-(IC11-NR)") (class "Default")
      (node (ref "C98") (pin "2") (pinfunction "2_2") (pintype "passive"))
      (node (ref "IC11") (pin "14") (pinfunction "NR_14") (pintype "passive"))
    )
    (net (code "21") (name "Net-(IC11-SENSE)") (class "Default")
      (node (ref "C97") (pin "2") (pinfunction "2_2") (pintype "passive"))
      (node (ref "IC11") (pin "1") (pinfunction "OUT_1") (pintype "power_in"))
      (node (ref "IC11") (pin "20") (pinfunction "OUT_20") (pintype "power_in"))
      (node (ref "IC11") (pin "3") (pinfunction "SENSE_3") (pintype "input"))
      (node (ref "L12") (pin "1") (pinfunction "1_1") (pintype "passive"))
    )
    (net (code "22") (name "Net-(IC12-NR)") (class "Default")
      (node (ref "C102") (pin "2") (pinfunction "2_2") (pintype "passive"))
      (node (ref "IC12") (pin "14") (pinfunction "NR_14") (pintype "passive"))
    )
    (net (code "23") (name "Net-(IC12-SENSE)") (class "Default")
      (node (ref "C101") (pin "2") (pinfunction "2_2") (pintype "passive"))
      (node (ref "IC12") (pin "1") (pinfunction "OUT_1") (pintype "power_in"))
      (node (ref "IC12") (pin "20") (pinfunction "OUT_20") (pintype "power_in"))
      (node (ref "IC12") (pin "3") (pinfunction "SENSE_3") (pintype "input"))
      (node (ref "L13") (pin "1") (pinfunction "1_1") (pintype "passive"))
    )
    (net (code "24") (name "P1V8") (class "Default")
      (node (ref "C92") (pin "2") (pinfunction "2_2") (pintype "passive"))
      (node (ref "IC10") (pin "1") (pinfunction "OUT_1") (pintype "power_in"))
      (node (ref "IC10") (pin "20") (pinfunction "OUT_20") (pintype "power_in"))
      (node (ref "IC10") (pin "3") (pinfunction "SENSE_3") (pintype "input"))
    )
    (net (code "25") (name "P3V3") (class "Default") (node (ref "L9") (pin "1") (pintype "passive")))
    (net (code "26") (name "P3V3_ADC1") (class "Default")
      (node (ref "L3") (pin "2") (pinfunction "2_2") (pintype "passive"))
    )
    (net (code "27") (name "P3V3_ADC2") (class "Default")
      (node (ref "L6") (pin "2") (pinfunction "2_2") (pintype "passive"))
    )
    (net (code "28") (name "P3V3_ADC3") (class "Default")
      (node (ref "L12") (pin "2") (pinfunction "2_2") (pintype "passive"))
    )
    (net (code "29") (name "P3V3_ADC4") (class "Default")
      (node (ref "L13") (pin "2") (pinfunction "2_2") (pintype "passive"))
    )
    (net (code "30") (name "P3V3_CLK") (class "Default")
      (node (ref "L7") (pin "2") (pinfunction "2_2") (pintype "passive"))
    )
    (net (code "31") (name "P4V0") (class "Default")
      (node (ref "C27") (pin "1") (pinfunction "1_1") (pintype "passive"))
      (node (ref "C32") (pin "1") (pinfunction "1_1") (pintype "passive"))
      (node (ref "C33") (pin "1") (pinfunction "1_1") (pintype "passive"))
      (node (ref "C34") (pin "1") (pinfunction "1_1") (pintype "passive"))
      (node (ref "C44") (pin "2") (pinfunction "2_2") (pintype "passive"))
      (node (ref "C52") (pin "1") (pinfunction "1_1") (pintype "passive"))
      (node (ref "C76") (pin "2") (pinfunction "2_2") (pintype "passive"))
      (node (ref "C81") (pin "1") (pinfunction "1_1") (pintype "passive"))
      (node (ref "C82") (pin "1") (pinfunction "1_1") (pintype "passive"))
      (node (ref "C96") (pin "2") (pinfunction "2_2") (pintype "passive"))
      (node (ref "IC7") (pin "13") (pinfunction "EN_13") (pintype "input"))
      (node (ref "IC7") (pin "15") (pinfunction "IN_15") (pintype "input"))
      (node (ref "IC7") (pin "16") (pinfunction "IN_16") (pintype "input"))
      (node (ref "IC8") (pin "J1") (pinfunction "VOUT_J1") (pintype "power_in"))
      (node (ref "IC8") (pin "J10") (pinfunction "VOUT_J10") (pintype "power_in"))
      (node (ref "IC8") (pin "J11") (pinfunction "VOUT_J11") (pintype "power_in"))
      (node (ref "IC8") (pin "J2") (pinfunction "VOUT_J2") (pintype "power_in"))
      (node (ref "IC8") (pin "J3") (pinfunction "VOUT_J3") (pintype "power_in"))
      (node (ref "IC8") (pin "J4") (pinfunction "VOUT_J4") (pintype "power_in"))
      (node (ref "IC8") (pin "J5") (pinfunction "VOUT_J5") (pintype "power_in"))
      (node (ref "IC8") (pin "J6") (pinfunction "VOUT_J6") (pintype "power_in"))
      (node (ref "IC8") (pin "J7") (pinfunction "VOUT_J7") (pintype "power_in"))
      (node (ref "IC8") (pin "J8") (pinfunction "VOUT_J8") (pintype "power_in"))
      (node (ref "IC8") (pin "J9") (pinfunction "VOUT_J9") (pintype "power_in"))
      (node (ref "IC8") (pin "K1") (pinfunction "VOUT_K1") (pintype "power_in"))
      (node (ref "IC8") (pin "K10") (pinfunction "VOUT_K10") (pintype "power_in"))
      (node (ref "IC8") (pin "K11") (pinfunction "VOUT_K11") (pintype "power_in"))
      (node (ref "IC8") (pin "K2") (pinfunction "VOUT_K2") (pintype "power_in"))
      (node (ref "IC8") (pin "K3") (pinfunction "VOUT_K3") (pintype "power_in"))
      (node (ref "IC8") (pin "K4") (pinfunction "VOUT_K4") (pintype "power_in"))
      (node (ref "IC8") (pin "K5") (pinfunction "VOUT_K5") (pintype "power_in"))
      (node (ref "IC8") (pin "K6") (pinfunction "VOUT_K6") (pintype "power_in"))
      (node (ref "IC8") (pin "K7") (pinfunction "VOUT_K7") (pintype "power_in"))
      (node (ref "IC8") (pin "K8") (pinfunction "VOUT_K8") (pintype "power_in"))
      (node (ref "IC8") (pin "K9") (pinfunction "VOUT_K9") (pintype "power_in"))
      (node (ref "IC8") (pin "L1") (pinfunction "VOUT_L1") (pintype "power_in"))
      (node (ref "IC8") (pin "L10") (pinfunction "VOUT_L10") (pintype "power_in"))
      (node (ref "IC8") (pin "L11") (pinfunction "VOUT_L11") (pintype "power_in"))
      (node (ref "IC8") (pin "L2") (pinfunction "VOUT_L2") (pintype "power_in"))
      (node (ref "IC8") (pin "L3") (pinfunction "VOUT_L3") (pintype "power_in"))
      (node (ref "IC8") (pin "L4") (pinfunction "VOUT_L4") (pintype "power_in"))
      (node (ref "IC8") (pin "L5") (pinfunction "VOUT_L5") (pintype "power_in"))
      (node (ref "IC8") (pin "L6") (pinfunction "VOUT_L6") (pintype "power_in"))
      (node (ref "IC8") (pin "L7") (pinfunction "VOUT_L7") (pintype "power_in"))
      (node (ref "IC8") (pin "L8") (pinfunction "VOUT_L8") (pintype "power_in"))
      (node (ref "IC8") (pin "L9") (pinfunction "VOUT_L9") (pintype "power_in"))
      (node (ref "IC8") (pin "M1") (pinfunction "VOUT_M1") (pintype "power_in"))
      (node (ref "IC8") (pin "M10") (pinfunction "VOUT_M10") (pintype "power_in"))
      (node (ref "IC8") (pin "M11") (pinfunction "VOUT_M11") (pintype "power_in"))
      (node (ref "IC8") (pin "M2") (pinfunction "VOUT_M2") (pintype "power_in"))
      (node (ref "IC8") (pin "M3") (pinfunction "VOUT_M3") (pintype "power_in"))
      (node (ref "IC8") (pin "M4") (pinfunction "VOUT_M4") (pintype "power_in"))
      (node (ref "IC8") (pin "M5") (pinfunction "VOUT_M5") (pintype "power_in"))
      (node (ref "IC8") (pin "M6") (pinfunction "VOUT_M6") (pintype "power_in"))
      (node (ref "IC8") (pin "M7") (pinfunction "VOUT_M7") (pintype "power_in"))
      (node (ref "IC8") (pin "M8") (pinfunction "VOUT_M8") (pintype "power_in"))
      (node (ref "IC8") (pin "M9") (pinfunction "VOUT_M9") (pintype "power_in"))
      (node (ref "L10") (pin "1") (pintype "passive"))
      (node (ref "L15") (pin "1") (pintype "passive"))
      (node (ref "R81") (pin "1") (pinfunction "1_1") (pintype "passive"))
    )
    (net (code "32") (name "P4V0_1") (class "Default")
      (node (ref "C75") (pin "2") (pinfunction "2_2") (pintype "passive"))
      (node (ref "C85") (pin "2") (pinfunction "2_2") (pintype "passive"))
      (node (ref "IC6") (pin "13") (pinfunction "EN_13") (pintype "input"))
      (node (ref "IC6") (pin "15") (pinfunction "IN_15") (pintype "input"))
      (node (ref "IC6") (pin "16") (pinfunction "IN_16") (pintype "input"))
      (node (ref "IC9") (pin "13") (pinfunction "EN_13") (pintype "input"))
      (node (ref "IC9") (pin "15") (pinfunction "IN_15") (pintype "input"))
      (node (ref "IC9") (pin "16") (pinfunction "IN_16") (pintype "input"))
      (node (ref "L10") (pin "2") (pintype "passive"))
    )
    (net (code "33") (name "P4V0_2") (class "Default")
      (node (ref "C100") (pin "2") (pinfunction "2_2") (pintype "passive"))
      (node (ref "C95") (pin "2") (pinfunction "2_2") (pintype "passive"))
      (node (ref "IC11") (pin "13") (pinfunction "EN_13") (pintype "input"))
      (node (ref "IC11") (pin "15") (pinfunction "IN_15") (pintype "input"))
      (node (ref "IC11") (pin "16") (pinfunction "IN_16") (pintype "input"))
      (node (ref "IC12") (pin "13") (pinfunction "EN_13") (pintype "input"))
      (node (ref "IC12") (pin "15") (pinfunction "IN_15") (pintype "input"))
      (node (ref "IC12") (pin "16") (pinfunction "IN_16") (pintype "input"))
      (node (ref "L15") (pin "2") (pintype "passive"))
    )
    (net (code "34") (name "P12V0") (class "Default")
      (node (ref "C28") (pin "1") (pinfunction "1_1") (pintype "passive"))
      (node (ref "C30") (pin "2") (pinfunction "2_2") (pintype "passive"))
      (node (ref "C35") (pin "1") (pinfunction "1_1") (pintype "passive"))
      (node (ref "C36") (pin "1") (pinfunction "1_1") (pintype "passive"))
      (node (ref "C38") (pin "2") (pinfunction "2_2") (pintype "passive"))
      (node (ref "C51") (pin "2") (pinfunction "2_2") (pintype "passive"))
      (node (ref "C88") (pin "2") (pinfunction "2_2") (pintype "passive"))
      (node (ref "IC8") (pin "A1") (pinfunction "VIN_A1") (pintype "input"))
      (node (ref "IC8") (pin "A2") (pinfunction "VIN_A2") (pintype "input"))
      (node (ref "IC8") (pin "A3") (pinfunction "VIN_A3") (pintype "input"))
      (node (ref "IC8") (pin "A4") (pinfunction "VIN_A4") (pintype "input"))
      (node (ref "IC8") (pin "A5") (pinfunction "VIN_A5") (pintype "input"))
      (node (ref "IC8") (pin "A6") (pinfunction "VIN_A6") (pintype "input"))
      (node (ref "IC8") (pin "B1") (pinfunction "VIN_B1") (pintype "input"))
      (node (ref "IC8") (pin "B2") (pinfunction "VIN_B2") (pintype "input"))
      (node (ref "IC8") (pin "B3") (pinfunction "VIN_B3") (pintype "input"))
      (node (ref "IC8") (pin "B4") (pinfunction "VIN_B4") (pintype "input"))
      (node (ref "IC8") (pin "B5") (pinfunction "VIN_B5") (pintype "input"))
      (node (ref "IC8") (pin "B6") (pinfunction "VIN_B6") (pintype "input"))
      (node (ref "IC8") (pin "C1") (pinfunction "VIN_C1") (pintype "input"))
      (node (ref "IC8") (pin "C2") (pinfunction "VIN_C2") (pintype "input"))
      (node (ref "IC8") (pin "C3") (pinfunction "VIN_C3") (pintype "input"))
      (node (ref "IC8") (pin "C4") (pinfunction "VIN_C4") (pintype "input"))
      (node (ref "IC8") (pin "C5") (pinfunction "VIN_C5") (pintype "input"))
      (node (ref "IC8") (pin "C6") (pinfunction "VIN_C6") (pintype "input"))
      (node (ref "R79") (pin "1") (pinfunction "1_1") (pintype "passive"))
    )
    (net (code "35") (name "VADJ") (class "Default")
      (node (ref "R78") (pin "1") (pinfunction "1_1") (pintype "passive"))
    )
    (net (code "36") (name "unconnected-(IC6-0P4V-Pad10)") (class "Default")
      (node (ref "IC6") (pin "10") (pinfunction "0P4V_10") (pintype "input+no_connect"))
    )
    (net (code "37") (name "unconnected-(IC6-0P8V-Pad9)") (class "Default")
      (node (ref "IC6") (pin "9") (pinfunction "0P8V_9") (pintype "input+no_connect"))
    )
    (net (code "38") (name "unconnected-(IC6-3P2V-Pad6)") (class "Default")
      (node (ref "IC6") (pin "6") (pinfunction "3P2V_6") (pintype "input+no_connect"))
    )
    (net (code "39") (name "unconnected-(IC6-6P4V1-Pad5)") (class "Default")
      (node (ref "IC6") (pin "5") (pinfunction "6P4V1_5") (pintype "input+no_connect"))
    )
    (net (code "40") (name "unconnected-(IC6-6P4V2-Pad4)") (class "Default")
      (node (ref "IC6") (pin "4") (pinfunction "6P4V2_4") (pintype "input+no_connect"))
    )
    (net (code "41") (name "unconnected-(IC6-NC-Pad2)") (class "Default")
      (node (ref "IC6") (pin "2") (pinfunction "NC_2") (pintype "passive"))
    )
    (net (code "42") (name "unconnected-(IC6-NC-Pad17)") (class "Default")
      (node (ref "IC6") (pin "17") (pinfunction "NC_17") (pintype "passive"))
    )
    (net (code "43") (name "unconnected-(IC6-NC-Pad18)") (class "Default")
      (node (ref "IC6") (pin "18") (pinfunction "NC_18") (pintype "passive"))
    )
    (net (code "44") (name "unconnected-(IC6-NC-Pad19)") (class "Default")
      (node (ref "IC6") (pin "19") (pinfunction "NC_19") (pintype "passive"))
    )
    (net (code "45") (name "unconnected-(IC7-0P4V-Pad10)") (class "Default")
      (node (ref "IC7") (pin "10") (pinfunction "0P4V_10") (pintype "input"))
    )
    (net (code "46") (name "unconnected-(IC7-0P8V-Pad9)") (class "Default")
      (node (ref "IC7") (pin "9") (pinfunction "0P8V_9") (pintype "input"))
    )
    (net (code "47") (name "unconnected-(IC7-3P2V-Pad6)") (class "Default")
      (node (ref "IC7") (pin "6") (pinfunction "3P2V_6") (pintype "input"))
    )
    (net (code "48") (name "unconnected-(IC7-6P4V1-Pad5)") (class "Default")
      (node (ref "IC7") (pin "5") (pinfunction "6P4V1_5") (pintype "input"))
    )
    (net (code "49") (name "unconnected-(IC7-6P4V2-Pad4)") (class "Default")
      (node (ref "IC7") (pin "4") (pinfunction "6P4V2_4") (pintype "input"))
    )
    (net (code "50") (name "unconnected-(IC7-NC-Pad2)") (class "Default")
      (node (ref "IC7") (pin "2") (pinfunction "NC_2") (pintype "passive"))
    )
    (net (code "51") (name "unconnected-(IC7-NC-Pad17)") (class "Default")
      (node (ref "IC7") (pin "17") (pinfunction "NC_17") (pintype "passive"))
    )
    (net (code "52") (name "unconnected-(IC7-NC-Pad18)") (class "Default")
      (node (ref "IC7") (pin "18") (pinfunction "NC_18") (pintype "passive"))
    )
    (net (code "53") (name "unconnected-(IC7-NC-Pad19)") (class "Default")
      (node (ref "IC7") (pin "19") (pinfunction "NC_19") (pintype "passive"))
    )
    (net (code "54") (name "unconnected-(IC8-COMP-PadA11)") (class "Default")
      (node (ref "IC8") (pin "A11") (pinfunction "COMP_A11") (pintype "passive"))
    )
    (net (code "55") (name "unconnected-(IC8-COMP-PadD11)") (class "Default")
      (node (ref "IC8") (pin "D11") (pinfunction "COMP_D11") (pintype "passive"))
    )
    (net (code "56") (name "unconnected-(IC8-MARG0-PadC12)") (class "Default")
      (node (ref "IC8") (pin "C12") (pinfunction "MARG0_C12") (pintype "input"))
    )
    (net (code "57") (name "unconnected-(IC8-MARG1-PadC11)") (class "Default")
      (node (ref "IC8") (pin "C11") (pinfunction "MARG1_C11") (pintype "input"))
    )
    (net (code "58") (name "unconnected-(IC8-MARG1-PadD12)") (class "Default")
      (node (ref "IC8") (pin "D12") (pinfunction "MARG1_D12") (pintype "input"))
    )
    (net (code "59") (name "unconnected-(IC8-NC-PadJ12)") (class "Default")
      (node (ref "IC8") (pin "J12") (pinfunction "NC_J12") (pintype "passive"))
    )
    (net (code "60") (name "unconnected-(IC8-NC-PadK12)") (class "Default")
      (node (ref "IC8") (pin "K12") (pinfunction "NC_K12") (pintype "passive"))
    )
    (net (code "61") (name "unconnected-(IC8-NC-PadL12)") (class "Default")
      (node (ref "IC8") (pin "L12") (pinfunction "NC_L12") (pintype "passive"))
    )
    (net (code "62") (name "unconnected-(IC8-PLLIN-PadA8)") (class "Default")
      (node (ref "IC8") (pin "A8") (pinfunction "PLLIN_A8") (pintype "input+no_connect"))
    )
    (net (code "63") (name "unconnected-(IC9-0P4V-Pad10)") (class "Default")
      (node (ref "IC9") (pin "10") (pinfunction "0P4V_10") (pintype "input+no_connect"))
    )
    (net (code "64") (name "unconnected-(IC9-0P8V-Pad9)") (class "Default")
      (node (ref "IC9") (pin "9") (pinfunction "0P8V_9") (pintype "input+no_connect"))
    )
    (net (code "65") (name "unconnected-(IC9-3P2V-Pad6)") (class "Default")
      (node (ref "IC9") (pin "6") (pinfunction "3P2V_6") (pintype "input+no_connect"))
    )
    (net (code "66") (name "unconnected-(IC9-6P4V1-Pad5)") (class "Default")
      (node (ref "IC9") (pin "5") (pinfunction "6P4V1_5") (pintype "input+no_connect"))
    )
    (net (code "67") (name "unconnected-(IC9-6P4V2-Pad4)") (class "Default")
      (node (ref "IC9") (pin "4") (pinfunction "6P4V2_4") (pintype "input+no_connect"))
    )
    (net (code "68") (name "unconnected-(IC9-NC-Pad2)") (class "Default")
      (node (ref "IC9") (pin "2") (pinfunction "NC_2") (pintype "passive"))
    )
    (net (code "69") (name "unconnected-(IC9-NC-Pad17)") (class "Default")
      (node (ref "IC9") (pin "17") (pinfunction "NC_17") (pintype "passive"))
    )
    (net (code "70") (name "unconnected-(IC9-NC-Pad18)") (class "Default")
      (node (ref "IC9") (pin "18") (pinfunction "NC_18") (pintype "passive"))
    )
    (net (code "71") (name "unconnected-(IC9-NC-Pad19)") (class "Default")
      (node (ref "IC9") (pin "19") (pinfunction "NC_19") (pintype "passive"))
    )
    (net (code "72") (name "unconnected-(IC10-0P1V-Pad12)") (class "Default")
      (node (ref "IC10") (pin "12") (pinfunction "0P1V_12") (pintype "input"))
    )
    (net (code "73") (name "unconnected-(IC10-0P2V-Pad11)") (class "Default")
      (node (ref "IC10") (pin "11") (pinfunction "0P2V_11") (pintype "input"))
    )
    (net (code "74") (name "unconnected-(IC10-0P8V-Pad9)") (class "Default")
      (node (ref "IC10") (pin "9") (pinfunction "0P8V_9") (pintype "input"))
    )
    (net (code "75") (name "unconnected-(IC10-1P6V-Pad8)") (class "Default")
      (node (ref "IC10") (pin "8") (pinfunction "1P6V_8") (pintype "input"))
    )
    (net (code "76") (name "unconnected-(IC10-3P2V-Pad6)") (class "Default")
      (node (ref "IC10") (pin "6") (pinfunction "3P2V_6") (pintype "input"))
    )
    (net (code "77") (name "unconnected-(IC10-6P4V1-Pad5)") (class "Default")
      (node (ref "IC10") (pin "5") (pinfunction "6P4V1_5") (pintype "input"))
    )
    (net (code "78") (name "unconnected-(IC10-6P4V2-Pad4)") (class "Default")
      (node (ref "IC10") (pin "4") (pinfunction "6P4V2_4") (pintype "input"))
    )
    (net (code "79") (name "unconnected-(IC10-NC-Pad2)") (class "Default")
      (node (ref "IC10") (pin "2") (pinfunction "NC_2") (pintype "passive"))
    )
    (net (code "80") (name "unconnected-(IC10-NC-Pad17)") (class "Default")
      (node (ref "IC10") (pin "17") (pinfunction "NC_17") (pintype "passive"))
    )
    (net (code "81") (name "unconnected-(IC10-NC-Pad18)") (class "Default")
      (node (ref "IC10") (pin "18") (pinfunction "NC_18") (pintype "passive"))
    )
    (net (code "82") (name "unconnected-(IC10-NC-Pad19)") (class "Default")
      (node (ref "IC10") (pin "19") (pinfunction "NC_19") (pintype "passive"))
    )
    (net (code "83") (name "unconnected-(IC11-0P4V-Pad10)") (class "Default")
      (node (ref "IC11") (pin "10") (pinfunction "0P4V_10") (pintype "input+no_connect"))
    )
    (net (code "84") (name "unconnected-(IC11-0P8V-Pad9)") (class "Default")
      (node (ref "IC11") (pin "9") (pinfunction "0P8V_9") (pintype "input+no_connect"))
    )
    (net (code "85") (name "unconnected-(IC11-3P2V-Pad6)") (class "Default")
      (node (ref "IC11") (pin "6") (pinfunction "3P2V_6") (pintype "input+no_connect"))
    )
    (net (code "86") (name "unconnected-(IC11-6P4V1-Pad5)") (class "Default")
      (node (ref "IC11") (pin "5") (pinfunction "6P4V1_5") (pintype "input+no_connect"))
    )
    (net (code "87") (name "unconnected-(IC11-6P4V2-Pad4)") (class "Default")
      (node (ref "IC11") (pin "4") (pinfunction "6P4V2_4") (pintype "input+no_connect"))
    )
    (net (code "88") (name "unconnected-(IC11-NC-Pad2)") (class "Default")
      (node (ref "IC11") (pin "2") (pinfunction "NC_2") (pintype "passive"))
    )
    (net (code "89") (name "unconnected-(IC11-NC-Pad17)") (class "Default")
      (node (ref "IC11") (pin "17") (pinfunction "NC_17") (pintype "passive"))
    )
    (net (code "90") (name "unconnected-(IC11-NC-Pad18)") (class "Default")
      (node (ref "IC11") (pin "18") (pinfunction "NC_18") (pintype "passive"))
    )
    (net (code "91") (name "unconnected-(IC11-NC-Pad19)") (class "Default")
      (node (ref "IC11") (pin "19") (pinfunction "NC_19") (pintype "passive"))
    )
    (net (code "92") (name "unconnected-(IC12-0P4V-Pad10)") (class "Default")
      (node (ref "IC12") (pin "10") (pinfunction "0P4V_10") (pintype "input+no_connect"))
    )
    (net (code "93") (name "unconnected-(IC12-0P8V-Pad9)") (class "Default")
      (node (ref "IC12") (pin "9") (pinfunction "0P8V_9") (pintype "input+no_connect"))
    )
    (net (code "94") (name "unconnected-(IC12-3P2V-Pad6)") (class "Default")
      (node (ref "IC12") (pin "6") (pinfunction "3P2V_6") (pintype "input+no_connect"))
    )
    (net (code "95") (name "unconnected-(IC12-6P4V1-Pad5)") (class "Default")
      (node (ref "IC12") (pin "5") (pinfunction "6P4V1_5") (pintype "input+no_connect"))
    )
    (net (code "96") (name "unconnected-(IC12-6P4V2-Pad4)") (class "Default")
      (node (ref "IC12") (pin "4") (pinfunction "6P4V2_4") (pintype "input+no_connect"))
    )
    (net (code "97") (name "unconnected-(IC12-NC-Pad2)") (class "Default")
      (node (ref "IC12") (pin "2") (pinfunction "NC_2") (pintype "passive"))
    )
    (net (code "98") (name "unconnected-(IC12-NC-Pad17)") (class "Default")
      (node (ref "IC12") (pin "17") (pinfunction "NC_17") (pintype "passive"))
    )
    (net (code "99") (name "unconnected-(IC12-NC-Pad18)") (class "Default")
      (node (ref "IC12") (pin "18") (pinfunction "NC_18") (pintype "passive"))
    )
    (net (code "100") (name "unconnected-(IC12-NC-Pad19)") (class "Default")
      (node (ref "IC12") (pin "19") (pinfunction "NC_19") (pintype "passive"))
    )
  )
)
